# esp32_master.net
KiCad netlist of a schematic drawn in Altium Designer
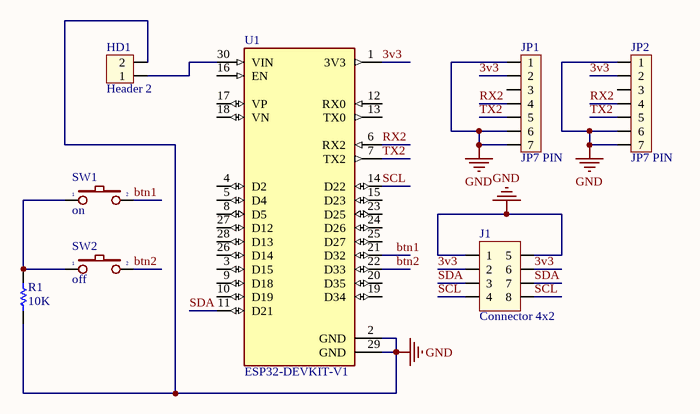
[diagram p0: esp32_master.SchDoc]

(export (version "E")
  (design (tool "Eeschema 10.0.6"))
  (components
    (comp (ref "HD1")
      (value "Header 2")
      (footprint "HED2")
      (description "Header 2 (Green)")
      (libsource (lib "syhaunguyen") (part "Hed2"))
    )
    (comp (ref "J1")
      (value "Connector 4x2")
      (footprint "JP4x2")
      (libsource (lib "syhaunguyen") (part "JP4x2"))
    )
    (comp (ref "JP1") (value "JP7 PIN") (footprint "JP7") (libsource (lib "syhaunguyen") (part "JP7")))
    (comp (ref "JP2") (value "JP7 PIN") (footprint "JP7") (libsource (lib "syhaunguyen") (part "JP7")))
    (comp (ref "R1")
      (value "10K")
      (footprint "R1/4W")
      (description "Resistor")
      (fields
        (field (name "MANUFACTURER") "Generic Components")
        (field (name "Comment") "Res1")
        (field (name "PUBLISHER") "Altium Hobart Technology Centre")
      )
      (libsource (lib "syhaunguyen") (part "Res1_1"))
    )
    (comp (ref "SW1")
      (value "on")
      (footprint "SW2")
      (description "Switch button 2 pin")
      (libsource (lib "syhaunguyen") (part "SW2"))
    )
    (comp (ref "SW2")
      (value "off")
      (footprint "SW2")
      (description "Switch button 2 pin")
      (libsource (lib "syhaunguyen") (part "SW2"))
    )
    (comp (ref "U1")
      (value "ESP32-DEVKIT-V1")
      (footprint "MODULE_ESP32_DEVKIT_V1")
      (fields (field (name "MF") "Do it"))
      (libsource (lib "ESP32-DEVKIT-V1") (part "ESP32-DEVKIT-V1"))
    )
  )
  (nets
    (net (code "1") (name "/3v3") (class "Default")
      (node (ref "J1") (pin "2") (pinfunction "2_2") (pintype "passive"))
      (node (ref "J1") (pin "6") (pinfunction "6_6") (pintype "passive"))
      (node (ref "JP1") (pin "2") (pinfunction "2_2") (pintype "passive"))
      (node (ref "JP2") (pin "2") (pinfunction "2_2") (pintype "passive"))
      (node (ref "U1") (pin "1") (pinfunction "3V3_1") (pintype "output"))
    )
    (net (code "2") (name "/RX2") (class "Default")
      (node (ref "JP1") (pin "4") (pinfunction "4_4") (pintype "passive"))
      (node (ref "JP2") (pin "4") (pinfunction "4_4") (pintype "passive"))
      (node (ref "U1") (pin "6") (pinfunction "RX2_6") (pintype "input"))
    )
    (net (code "3") (name "/SCL") (class "Default")
      (node (ref "J1") (pin "4") (pinfunction "4_4") (pintype "passive"))
      (node (ref "J1") (pin "8") (pinfunction "8_8") (pintype "passive"))
      (node (ref "U1") (pin "14") (pinfunction "D22_14") (pintype "bidirectional"))
    )
    (net (code "4") (name "/SDA") (class "Default")
      (node (ref "J1") (pin "3") (pinfunction "3_3") (pintype "passive"))
      (node (ref "J1") (pin "7") (pinfunction "7_7") (pintype "passive"))
      (node (ref "U1") (pin "11") (pinfunction "D21_11") (pintype "bidirectional"))
    )
    (net (code "5") (name "/TX2") (class "Default")
      (node (ref "JP1") (pin "5") (pinfunction "5_5") (pintype "passive"))
      (node (ref "JP2") (pin "5") (pinfunction "5_5") (pintype "passive"))
      (node (ref "U1") (pin "7") (pinfunction "TX2_7") (pintype "output"))
    )
    (net (code "6") (name "/btn1") (class "Default")
      (node (ref "SW1") (pin "2") (pinfunction "2_2") (pintype "passive"))
      (node (ref "U1") (pin "21") (pinfunction "D32_21") (pintype "bidirectional"))
    )
    (net (code "7") (name "/btn2") (class "Default")
      (node (ref "SW2") (pin "2") (pinfunction "2_2") (pintype "passive"))
      (node (ref "U1") (pin "22") (pinfunction "D33_22") (pintype "bidirectional"))
    )
    (net (code "8") (name "GND") (class "Default")
      (node (ref "HD1") (pin "2") (pinfunction "2_2") (pintype "passive"))
      (node (ref "J1") (pin "1") (pinfunction "1_1") (pintype "passive"))
      (node (ref "J1") (pin "5") (pinfunction "5_5") (pintype "passive"))
      (node (ref "JP1") (pin "1") (pinfunction "1_1") (pintype "passive"))
      (node (ref "JP1") (pin "6") (pinfunction "6_6") (pintype "passive"))
      (node (ref "JP1") (pin "7") (pinfunction "7_7") (pintype "passive"))
      (node (ref "JP2") (pin "1") (pinfunction "1_1") (pintype "passive"))
      (node (ref "JP2") (pin "6") (pinfunction "6_6") (pintype "passive"))
      (node (ref "JP2") (pin "7") (pinfunction "7_7") (pintype "passive"))
      (node (ref "R1") (pin "2") (pinfunction "2_2") (pintype "passive"))
      (node (ref "U1") (pin "2") (pinfunction "GND_2") (pintype "power_in"))
      (node (ref "U1") (pin "29") (pinfunction "GND_29") (pintype "power_in"))
    )
    (net (code "9") (name "Net-(R1-Pad1)") (class "Default")
      (node (ref "R1") (pin "1") (pinfunction "1_1") (pintype "passive"))
      (node (ref "SW1") (pin "1") (pinfunction "1_1") (pintype "passive"))
      (node (ref "SW2") (pin "1") (pinfunction "1_1") (pintype "passive"))
    )
    (net (code "10") (name "Net-(U1-VIN)") (class "Default")
      (node (ref "HD1") (pin "1") (pinfunction "1_1") (pintype "passive"))
      (node (ref "U1") (pin "30") (pinfunction "VIN_30") (pintype "input"))
    )
    (net (code "11") (name "unconnected-(JP1-Pad3)") (class "Default")
      (node (ref "JP1") (pin "3") (pinfunction "3_3") (pintype "passive"))
    )
    (net (code "12") (name "unconnected-(JP2-Pad3)") (class "Default")
      (node (ref "JP2") (pin "3") (pinfunction "3_3") (pintype "passive"))
    )
    (net (code "13") (name "unconnected-(U1-D2-Pad4)") (class "Default")
      (node (ref "U1") (pin "4") (pinfunction "D2_4") (pintype "bidirectional"))
    )
    (net (code "14") (name "unconnected-(U1-D4-Pad5)") (class "Default")
      (node (ref "U1") (pin "5") (pinfunction "D4_5") (pintype "bidirectional"))
    )
    (net (code "15") (name "unconnected-(U1-D5-Pad8)") (class "Default")
      (node (ref "U1") (pin "8") (pinfunction "D5_8") (pintype "bidirectional"))
    )
    (net (code "16") (name "unconnected-(U1-D12-Pad27)") (class "Default")
      (node (ref "U1") (pin "27") (pinfunction "D12_27") (pintype "bidirectional"))
    )
    (net (code "17") (name "unconnected-(U1-D13-Pad28)") (class "Default")
      (node (ref "U1") (pin "28") (pinfunction "D13_28") (pintype "bidirectional"))
    )
    (net (code "18") (name "unconnected-(U1-D14-Pad26)") (class "Default")
      (node (ref "U1") (pin "26") (pinfunction "D14_26") (pintype "bidirectional"))
    )
    (net (code "19") (name "unconnected-(U1-D15-Pad3)") (class "Default")
      (node (ref "U1") (pin "3") (pinfunction "D15_3") (pintype "bidirectional"))
    )
    (net (code "20") (name "unconnected-(U1-D18-Pad9)") (class "Default")
      (node (ref "U1") (pin "9") (pinfunction "D18_9") (pintype "bidirectional"))
    )
    (net (code "21") (name "unconnected-(U1-D19-Pad10)") (class "Default")
      (node (ref "U1") (pin "10") (pinfunction "D19_10") (pintype "bidirectional"))
    )
    (net (code "22") (name "unconnected-(U1-D23-Pad15)") (class "Default")
      (node (ref "U1") (pin "15") (pinfunction "D23_15") (pintype "bidirectional"))
    )
    (net (code "23") (name "unconnected-(U1-D25-Pad23)") (class "Default")
      (node (ref "U1") (pin "23") (pinfunction "D25_23") (pintype "bidirectional"))
    )
    (net (code "24") (name "unconnected-(U1-D26-Pad24)") (class "Default")
      (node (ref "U1") (pin "24") (pinfunction "D26_24") (pintype "bidirectional"))
    )
    (net (code "25") (name "unconnected-(U1-D27-Pad25)") (class "Default")
      (node (ref "U1") (pin "25") (pinfunction "D27_25") (pintype "bidirectional"))
    )
    (net (code "26") (name "unconnected-(U1-D34-Pad19)") (class "Default")
      (node (ref "U1") (pin "19") (pinfunction "D34_19") (pintype "bidirectional"))
    )
    (net (code "27") (name "unconnected-(U1-D35-Pad20)") (class "Default")
      (node (ref "U1") (pin "20") (pinfunction "D35_20") (pintype "bidirectional"))
    )
    (net (code "28") (name "unconnected-(U1-EN-Pad16)") (class "Default")
      (node (ref "U1") (pin "16") (pinfunction "EN_16") (pintype "input"))
    )
    (net (code "29") (name "unconnected-(U1-RX0-Pad12)") (class "Default")
      (node (ref "U1") (pin "12") (pinfunction "RX0_12") (pintype "input"))
    )
    (net (code "30") (name "unconnected-(U1-TX0-Pad13)") (class "Default")
      (node (ref "U1") (pin "13") (pinfunction "TX0_13") (pintype "output"))
    )
    (net (code "31") (name "unconnected-(U1-VN-Pad18)") (class "Default")
      (node (ref "U1") (pin "18") (pinfunction "VN_18") (pintype "bidirectional"))
    )
    (net (code "32") (name "unconnected-(U1-VP-Pad17)") (class "Default")
      (node (ref "U1") (pin "17") (pinfunction "VP_17") (pintype "bidirectional"))
    )
  )
)
